# CANtoCAN.net
KiCad netlist of a schematic drawn in Altium Designer
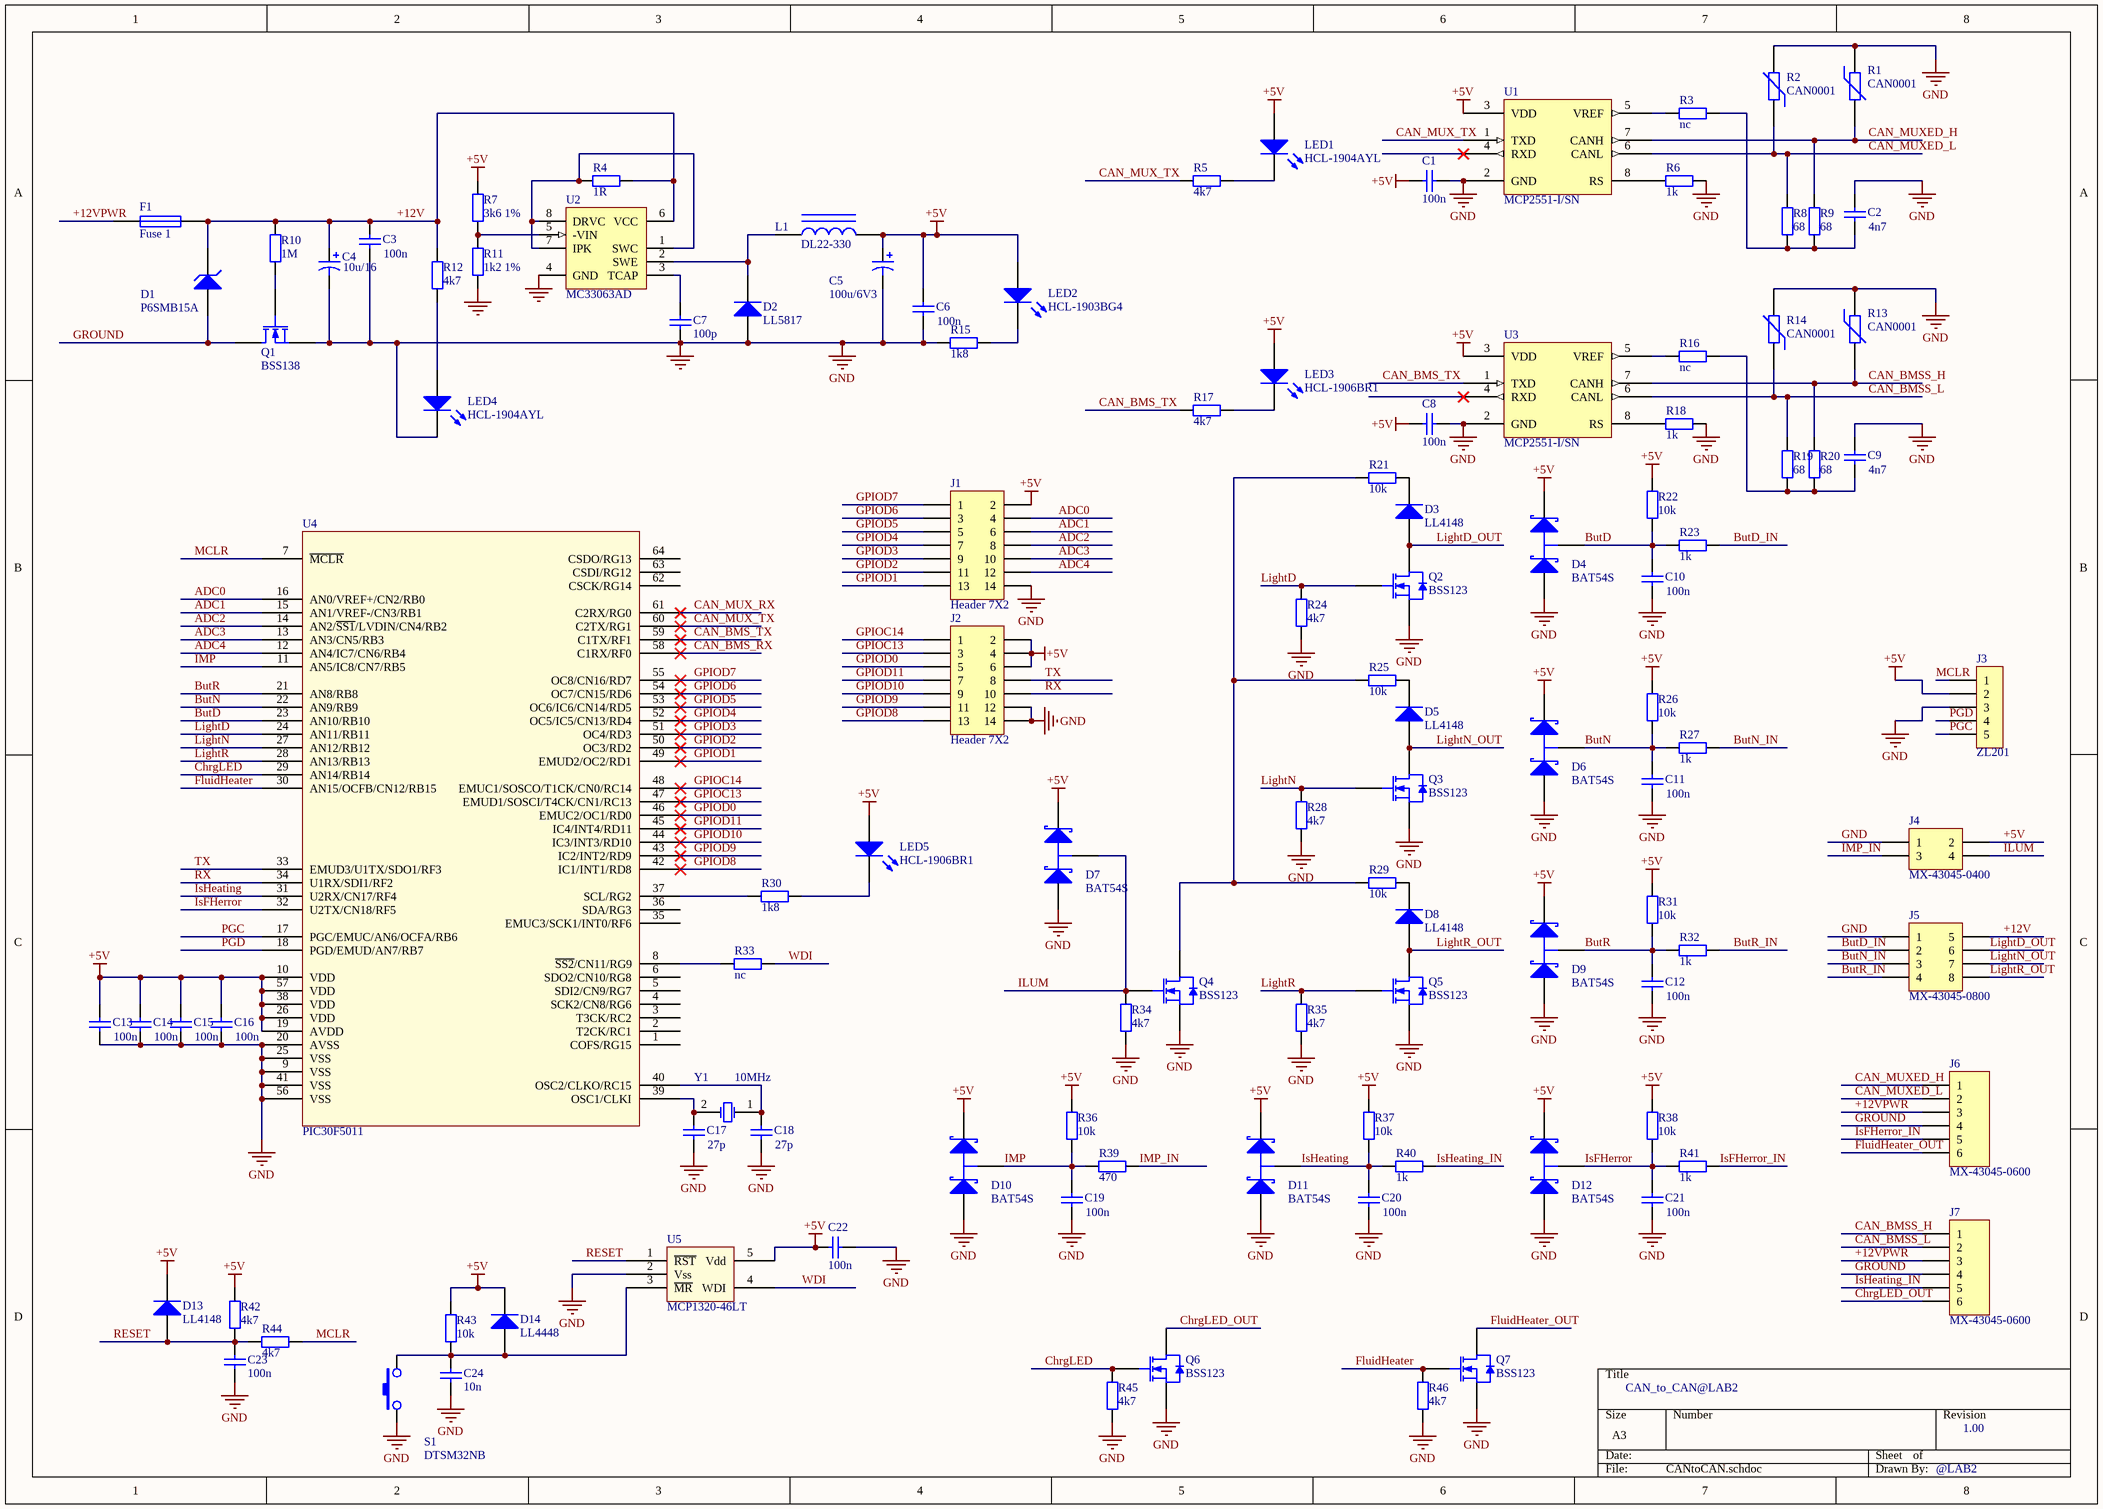
[diagram p0: CANtoCAN.schdoc]

(export (version "E")
  (design (tool "Eeschema 10.0.6"))
  (components
    (comp (ref "C1")
      (value "100n")
      (footprint "0603")
      (description "Capacitor")
      (libsource (lib "Miscellaneous Devices") (part "Cap"))
    )
    (comp (ref "C2")
      (value "4n7")
      (footprint "0603")
      (description "Capacitor")
      (libsource (lib "Miscellaneous Devices") (part "Cap"))
    )
    (comp (ref "C3")
      (value "100n")
      (footprint "0402-A")
      (description "Capacitor")
      (libsource (lib "Miscellaneous Devices") (part "Cap"))
    )
    (comp (ref "C4")
      (value "10u/16")
      (footprint "0402-A")
      (description "Polarized Capacitor (Radial)")
      (libsource (lib "Miscellaneous Devices") (part "Cap Pol1"))
    )
    (comp (ref "C5")
      (value "100u/6V3")
      (footprint "0402-A")
      (description "Polarized Capacitor (Radial)")
      (libsource (lib "Miscellaneous Devices") (part "Cap Pol1"))
    )
    (comp (ref "C6")
      (value "100n")
      (footprint "0603")
      (description "Capacitor")
      (libsource (lib "Miscellaneous Devices") (part "Cap"))
    )
    (comp (ref "C7")
      (value "100p")
      (footprint "0603")
      (description "Capacitor")
      (libsource (lib "Miscellaneous Devices") (part "Cap"))
    )
    (comp (ref "C8")
      (value "100n")
      (footprint "0603")
      (description "Capacitor")
      (libsource (lib "Miscellaneous Devices") (part "Cap"))
    )
    (comp (ref "C9")
      (value "4n7")
      (footprint "0603")
      (description "Capacitor")
      (libsource (lib "Miscellaneous Devices") (part "Cap"))
    )
    (comp (ref "C10")
      (value "100n")
      (footprint "0603")
      (description "Capacitor")
      (libsource (lib "Miscellaneous Devices") (part "Cap"))
    )
    (comp (ref "C11")
      (value "100n")
      (footprint "0603")
      (description "Capacitor")
      (libsource (lib "Miscellaneous Devices") (part "Cap"))
    )
    (comp (ref "C12")
      (value "100n")
      (footprint "0603")
      (description "Capacitor")
      (libsource (lib "Miscellaneous Devices") (part "Cap"))
    )
    (comp (ref "C13")
      (value "100n")
      (footprint "0603")
      (description "Capacitor")
      (libsource (lib "Miscellaneous Devices") (part "Cap"))
    )
    (comp (ref "C14")
      (value "100n")
      (footprint "0603")
      (description "Capacitor")
      (libsource (lib "Miscellaneous Devices") (part "Cap"))
    )
    (comp (ref "C15")
      (value "100n")
      (footprint "0603")
      (description "Capacitor")
      (libsource (lib "Miscellaneous Devices") (part "Cap"))
    )
    (comp (ref "C16")
      (value "100n")
      (footprint "0603")
      (description "Capacitor")
      (libsource (lib "Miscellaneous Devices") (part "Cap"))
    )
    (comp (ref "C17")
      (value "27p")
      (footprint "0603")
      (description "Capacitor")
      (libsource (lib "Miscellaneous Devices") (part "Cap"))
    )
    (comp (ref "C18")
      (value "27p")
      (footprint "0603")
      (description "Capacitor")
      (libsource (lib "Miscellaneous Devices") (part "Cap"))
    )
    (comp (ref "C19")
      (value "100n")
      (footprint "0603")
      (description "Capacitor")
      (libsource (lib "Miscellaneous Devices") (part "Cap"))
    )
    (comp (ref "C20")
      (value "100n")
      (footprint "0603")
      (description "Capacitor")
      (libsource (lib "Miscellaneous Devices") (part "Cap"))
    )
    (comp (ref "C21")
      (value "100n")
      (footprint "0603")
      (description "Capacitor")
      (libsource (lib "Miscellaneous Devices") (part "Cap"))
    )
    (comp (ref "C22")
      (value "100n")
      (footprint "0603")
      (description "Capacitor")
      (libsource (lib "Miscellaneous Devices") (part "Cap"))
    )
    (comp (ref "C23")
      (value "100n")
      (footprint "0603")
      (description "Capacitor")
      (libsource (lib "Miscellaneous Devices") (part "Cap"))
    )
    (comp (ref "C24")
      (value "10n")
      (footprint "0603")
      (description "Capacitor")
      (libsource (lib "Miscellaneous Devices") (part "Cap"))
    )
    (comp (ref "D1")
      (value "P6SMB15A")
      (footprint "6-0805_M")
      (description "Zener Diode")
      (libsource (lib "Miscellaneous Devices") (part "D Zener"))
    )
    (comp (ref "D2")
      (value "LL5817")
      (footprint "6-0805_M")
      (description "High Conductance Fast Diode")
      (libsource (lib "FSC Discrete Diode") (part "1N4148"))
    )
    (comp (ref "D3")
      (value "LL4148")
      (footprint "6-0805_N")
      (description "High Conductance Fast Diode")
      (libsource (lib "FSC Discrete Diode") (part "1N4148"))
    )
    (comp (ref "D4")
      (value "BAT54S")
      (footprint "SOT23_M")
      (description "Schottky Barrier Double Diode")
      (libsource (lib "Philips Discrete Diode - Schottky") (part "BAT54S"))
    )
    (comp (ref "D5")
      (value "LL4148")
      (footprint "3.2X1.6X1.1")
      (description "High Conductance Fast Diode")
      (libsource (lib "FSC Discrete Diode") (part "1N4148"))
    )
    (comp (ref "D6")
      (value "BAT54S")
      (footprint "SOT-23B_M")
      (description "Schottky Barrier Double Diode")
      (libsource (lib "Philips Discrete Diode - Schottky") (part "BAT54S"))
    )
    (comp (ref "D7")
      (value "BAT54S")
      (footprint "SOT23_N")
      (description "Schottky Barrier Double Diode")
      (libsource (lib "Philips Discrete Diode - Schottky") (part "BAT54S"))
    )
    (comp (ref "D8")
      (value "LL4148")
      (footprint "3.2X1.6X1.1")
      (description "High Conductance Fast Diode")
      (libsource (lib "FSC Discrete Diode") (part "1N4148"))
    )
    (comp (ref "D9")
      (value "BAT54S")
      (footprint "SOT23_M")
      (description "Schottky Barrier Double Diode")
      (libsource (lib "Philips Discrete Diode - Schottky") (part "BAT54S"))
    )
    (comp (ref "D10")
      (value "BAT54S")
      (footprint "SOT23_M")
      (description "Schottky Barrier Double Diode")
      (libsource (lib "Philips Discrete Diode - Schottky") (part "BAT54S"))
    )
    (comp (ref "D11")
      (value "BAT54S")
      (footprint "SOT23_M")
      (description "Schottky Barrier Double Diode")
      (libsource (lib "Philips Discrete Diode - Schottky") (part "BAT54S"))
    )
    (comp (ref "D12")
      (value "BAT54S")
      (footprint "SOT23_N")
      (description "Schottky Barrier Double Diode")
      (libsource (lib "Philips Discrete Diode - Schottky") (part "BAT54S"))
    )
    (comp (ref "D13")
      (value "LL4148")
      (footprint "6-0805_M")
      (description "High Conductance Fast Diode")
      (libsource (lib "FSC Discrete Diode") (part "1N4148"))
    )
    (comp (ref "D14")
      (value "LL4448")
      (footprint "3.2X1.6X1.1")
      (description "Default Diode")
      (libsource (lib "Miscellaneous Devices") (part "Diode"))
    )
    (comp (ref "F1")
      (value "Fuse 1")
      (footprint "6-0805_N")
      (description "Fuse")
      (libsource (lib "Miscellaneous Devices") (part "Fuse 1"))
    )
    (comp (ref "J1")
      (value "Header 7X2")
      (footprint "HDR2X7")
      (description "Header, 7-Pin, Dual row")
      (libsource (lib "Miscellaneous Connectors") (part "Header 7X2"))
    )
    (comp (ref "J2")
      (value "Header 7X2")
      (footprint "HDR2X7")
      (description "Header, 7-Pin, Dual row")
      (libsource (lib "Miscellaneous Connectors") (part "Header 7X2"))
    )
    (comp (ref "J3")
      (value "ZL201")
      (footprint "HDR1X5")
      (description "Connector")
      (libsource (lib "*") (part "CON5"))
    )
    (comp (ref "J4")
      (value "MX-43045-0400")
      (footprint "MHDR2X2")
      (description "Header, 2-Pin, Dual row")
      (libsource (lib "Miscellaneous Connectors") (part "Header 2X2"))
    )
    (comp (ref "J5")
      (value "MX-43045-0800")
      (footprint "HDR2X4")
      (description "Header, 4-Pin, Dual row")
      (libsource (lib "Miscellaneous Connectors") (part "Header 4X2A"))
    )
    (comp (ref "J6")
      (value "MX-43045-0600")
      (footprint "HDR1X8")
      (description "Header, 6-Pin")
      (libsource (lib "Miscellaneous Connectors") (part "Header 6"))
    )
    (comp (ref "J7")
      (value "MX-43045-0600")
      (footprint "MHDR1X6")
      (description "Header, 6-Pin")
      (libsource (lib "Miscellaneous Connectors") (part "Header 6"))
    )
    (comp (ref "L1")
      (value "DL22-330")
      (footprint "0402-A")
      (description "Magnetic-Core Inductor")
      (libsource (lib "Miscellaneous Devices") (part "Inductor Iron"))
    )
    (comp (ref "LED1")
      (value "HCL-1904AYL")
      (footprint "0603")
      (description "Typical BLUE SiC LED")
      (libsource (lib "Miscellaneous Devices") (part "LED3"))
    )
    (comp (ref "LED2")
      (value "HCL-1903BG4")
      (footprint "0603")
      (description "Typical BLUE SiC LED")
      (libsource (lib "Miscellaneous Devices") (part "LED3"))
    )
    (comp (ref "LED3")
      (value "HCL-1906BR1")
      (footprint "0603")
      (description "Typical BLUE SiC LED")
      (libsource (lib "Miscellaneous Devices") (part "LED3"))
    )
    (comp (ref "LED4")
      (value "HCL-1904AYL")
      (footprint "6-0805_M")
      (description "Typical BLUE SiC LED")
      (libsource (lib "Miscellaneous Devices") (part "LED3"))
    )
    (comp (ref "LED5")
      (value "HCL-1906BR1")
      (footprint "0603")
      (description "Typical BLUE SiC LED")
      (libsource (lib "Miscellaneous Devices") (part "LED3"))
    )
    (comp (ref "Q1")
      (value "BSS138")
      (footprint "SOT23_N")
      (description "N-Channel Enhancement Mode Vertical DMOS FET")
      (libsource (lib "Zetex Discrete MOSFET") (part "BSS138"))
    )
    (comp (ref "Q2")
      (value "BSS123")
      (footprint "SOT23_N")
      (description "N-channel Enhancement Mode Vertical D-MOSFET")
      (libsource (lib "Philips Discrete MOSFET - Low Power") (part "BSS123"))
    )
    (comp (ref "Q3")
      (value "BSS123")
      (footprint "SOT23_M")
      (description "N-channel Enhancement Mode Vertical D-MOSFET")
      (libsource (lib "Philips Discrete MOSFET - Low Power") (part "BSS123"))
    )
    (comp (ref "Q4")
      (value "BSS123")
      (footprint "SOT23_N")
      (description "N-channel Enhancement Mode Vertical D-MOSFET")
      (libsource (lib "Philips Discrete MOSFET - Low Power") (part "BSS123"))
    )
    (comp (ref "Q5")
      (value "BSS123")
      (footprint "SOT23_L")
      (description "N-channel Enhancement Mode Vertical D-MOSFET")
      (libsource (lib "Philips Discrete MOSFET - Low Power") (part "BSS123"))
    )
    (comp (ref "Q6")
      (value "BSS123")
      (footprint "SOT23_N")
      (description "N-channel Enhancement Mode Vertical D-MOSFET")
      (libsource (lib "Philips Discrete MOSFET - Low Power") (part "BSS123"))
    )
    (comp (ref "Q7")
      (value "BSS123")
      (footprint "SOT23_N")
      (description "N-channel Enhancement Mode Vertical D-MOSFET")
      (libsource (lib "Philips Discrete MOSFET - Low Power") (part "BSS123"))
    )
    (comp (ref "R1")
      (value "CAN0001")
      (footprint "0603")
      (description "Varistor (Voltage-Sensitive Resistor)")
      (libsource (lib "Miscellaneous Devices") (part "Res Varistor"))
    )
    (comp (ref "R2")
      (value "CAN0001")
      (footprint "0603")
      (description "Varistor (Voltage-Sensitive Resistor)")
      (libsource (lib "Miscellaneous Devices") (part "Res Varistor"))
    )
    (comp (ref "R3")
      (value "nc")
      (footprint "0603")
      (description "Resistor")
      (libsource (lib "") (part "Res2_1"))
    )
    (comp (ref "R4")
      (value "1R")
      (footprint "0603")
      (description "Resistor")
      (libsource (lib "") (part "Res2_1"))
    )
    (comp (ref "R5")
      (value "4k7")
      (footprint "0603")
      (description "Resistor")
      (libsource (lib "Miscellaneous Devices") (part "Res2"))
    )
    (comp (ref "R6")
      (value "1k")
      (footprint "0603")
      (description "Resistor")
      (libsource (lib "") (part "Res2_1"))
    )
    (comp (ref "R7")
      (value "3k6 1%")
      (footprint "0603")
      (description "Resistor")
      (libsource (lib "") (part "Res2_2"))
    )
    (comp (ref "R8")
      (value "68")
      (footprint "0603")
      (description "Resistor")
      (libsource (lib "") (part "Res2_2"))
    )
    (comp (ref "R9")
      (value "68")
      (footprint "0603")
      (description "Resistor")
      (libsource (lib "") (part "Res2_2"))
    )
    (comp (ref "R10")
      (value "1M")
      (footprint "0603")
      (description "Resistor")
      (libsource (lib "") (part "Res2_2"))
    )
    (comp (ref "R11")
      (value "1k2 1%")
      (footprint "0603")
      (description "Resistor")
      (libsource (lib "") (part "Res2_3"))
    )
    (comp (ref "R12")
      (value "4k7")
      (footprint "0603")
      (description "Resistor")
      (libsource (lib "") (part "Res2_2"))
    )
    (comp (ref "R13")
      (value "CAN0001")
      (footprint "0603")
      (description "Varistor (Voltage-Sensitive Resistor)")
      (libsource (lib "Miscellaneous Devices") (part "Res Varistor"))
    )
    (comp (ref "R14")
      (value "CAN0001")
      (footprint "0603")
      (description "Varistor (Voltage-Sensitive Resistor)")
      (libsource (lib "Miscellaneous Devices") (part "Res Varistor"))
    )
    (comp (ref "R15")
      (value "1k8")
      (footprint "0603")
      (description "Resistor")
      (libsource (lib "Miscellaneous Devices") (part "Res2"))
    )
    (comp (ref "R16")
      (value "nc")
      (footprint "0603")
      (description "Resistor")
      (libsource (lib "") (part "Res2_1"))
    )
    (comp (ref "R17")
      (value "4k7")
      (footprint "0603")
      (description "Resistor")
      (libsource (lib "Miscellaneous Devices") (part "Res2"))
    )
    (comp (ref "R18")
      (value "1k")
      (footprint "0603")
      (description "Resistor")
      (libsource (lib "") (part "Res2_1"))
    )
    (comp (ref "R19")
      (value "68")
      (footprint "0603")
      (description "Resistor")
      (libsource (lib "") (part "Res2_2"))
    )
    (comp (ref "R20")
      (value "68")
      (footprint "0603")
      (description "Resistor")
      (libsource (lib "") (part "Res2_2"))
    )
    (comp (ref "R21")
      (value "10k")
      (footprint "0603")
      (description "Resistor")
      (libsource (lib "") (part "Res2_1"))
    )
    (comp (ref "R22")
      (value "10k")
      (footprint "0603")
      (description "Resistor")
      (libsource (lib "") (part "Res2_2"))
    )
    (comp (ref "R23")
      (value "1k")
      (footprint "0603")
      (description "Resistor")
      (libsource (lib "Miscellaneous Devices") (part "Res2"))
    )
    (comp (ref "R24")
      (value "4k7")
      (footprint "0603")
      (description "Resistor")
      (libsource (lib "") (part "Res2_2"))
    )
    (comp (ref "R25")
      (value "10k")
      (footprint "0603")
      (description "Resistor")
      (libsource (lib "") (part "Res2_1"))
    )
    (comp (ref "R26")
      (value "10k")
      (footprint "0603")
      (description "Resistor")
      (libsource (lib "") (part "Res2_2"))
    )
    (comp (ref "R27")
      (value "1k")
      (footprint "0603")
      (description "Resistor")
      (libsource (lib "Miscellaneous Devices") (part "Res2"))
    )
    (comp (ref "R28")
      (value "4k7")
      (footprint "0603")
      (description "Resistor")
      (libsource (lib "") (part "Res2_2"))
    )
    (comp (ref "R29")
      (value "10k")
      (footprint "0603")
      (description "Resistor")
      (libsource (lib "") (part "Res2_1"))
    )
    (comp (ref "R30")
      (value "1k8")
      (footprint "0603")
      (description "Resistor")
      (libsource (lib "Miscellaneous Devices") (part "Res2"))
    )
    (comp (ref "R31")
      (value "10k")
      (footprint "0603")
      (description "Resistor")
      (libsource (lib "") (part "Res2_2"))
    )
    (comp (ref "R32")
      (value "1k")
      (footprint "0603")
      (description "Resistor")
      (libsource (lib "Miscellaneous Devices") (part "Res2"))
    )
    (comp (ref "R33")
      (value "nc")
      (footprint "0603")
      (description "Resistor")
      (libsource (lib "Miscellaneous Devices") (part "Res2"))
    )
    (comp (ref "R34")
      (value "4k7")
      (footprint "0603")
      (description "Resistor")
      (libsource (lib "") (part "Res2_2"))
    )
    (comp (ref "R35")
      (value "4k7")
      (footprint "0603")
      (description "Resistor")
      (libsource (lib "") (part "Res2_2"))
    )
    (comp (ref "R36")
      (value "10k")
      (footprint "0603")
      (description "Resistor")
      (libsource (lib "") (part "Res2_2"))
    )
    (comp (ref "R37")
      (value "10k")
      (footprint "0603")
      (description "Resistor")
      (libsource (lib "") (part "Res2_2"))
    )
    (comp (ref "R38")
      (value "10k")
      (footprint "0603")
      (description "Resistor")
      (libsource (lib "") (part "Res2_2"))
    )
    (comp (ref "R39")
      (value "470")
      (footprint "0603")
      (description "Resistor")
      (libsource (lib "Miscellaneous Devices") (part "Res2"))
    )
    (comp (ref "R40")
      (value "1k")
      (footprint "0603")
      (description "Resistor")
      (libsource (lib "Miscellaneous Devices") (part "Res2"))
    )
    (comp (ref "R41")
      (value "1k")
      (footprint "0603")
      (description "Resistor")
      (libsource (lib "Miscellaneous Devices") (part "Res2"))
    )
    (comp (ref "R42")
      (value "4k7")
      (footprint "0603")
      (description "Resistor")
      (libsource (lib "") (part "Res2_2"))
    )
    (comp (ref "R43")
      (value "10k")
      (footprint "0603")
      (description "Resistor")
      (libsource (lib "") (part "Res2_3"))
    )
    (comp (ref "R44")
      (value "4k7")
      (footprint "0603")
      (description "Resistor")
      (libsource (lib "Miscellaneous Devices") (part "Res2"))
    )
    (comp (ref "R45")
      (value "4k7")
      (footprint "0603")
      (description "Resistor")
      (libsource (lib "") (part "Res2_2"))
    )
    (comp (ref "R46")
      (value "4k7")
      (footprint "0603")
      (description "Resistor")
      (libsource (lib "") (part "Res2_2"))
    )
    (comp (ref "S1")
      (value "DTSM32NB")
      (footprint "0402")
      (description "Switch PushButton")
      (libsource (lib "*") (part "PUSHB"))
    )
    (comp (ref "U1")
      (value "MCP2551-I/SN")
      (footprint "SO8_L")
      (description "High Speed CAN Transceiver, 8-Pin Plastic SOIC, Industrial Grade")
      (libsource (lib "Microchip Interface Line Transceiver") (part "MCP2551-I/SN"))
    )
    (comp (ref "U2")
      (value "MC33063AD")
      (footprint "SO8_N")
      (description "DC-to-DC Converter Control Circuit")
      (libsource (lib "Motorola Power Mgt DC-DC Converter") (part "MC33063AD"))
    )
    (comp (ref "U3")
      (value "MCP2551-I/SN")
      (footprint "SO8_L")
      (description "High Speed CAN Transceiver, 8-Pin Plastic SOIC, Industrial Grade")
      (libsource (lib "Microchip Interface Line Transceiver") (part "MCP2551-I/SN"))
    )
    (comp (ref "U4")
      (value "PIC30F5011")
      (footprint "QFP80P1600X1600X120-64N")
      (description "PIC30F5011 - Up")
      (libsource (lib "X-Tro's Misc") (part "PIC30F5011"))
    )
    (comp (ref "U5")
      (value "MCP1320-46LT")
      (footprint "SOP5(6)")
      (libsource (lib "X-Tro's Misc") (part "MCP1320"))
    )
    (comp (ref "Y1")
      (value "10MHz")
      (footprint "AXIAL-0.3")
      (description "Crystal Oscillator")
      (libsource (lib "Miscellaneous Devices") (part "XTAL"))
    )
  )
  (nets
    (net (code "1") (name "+5V") (class "Default")
      (node (ref "C1") (pin "1") (pinfunction "1_1") (pintype "passive"))
      (node (ref "C13") (pin "1") (pinfunction "1_1") (pintype "passive"))
      (node (ref "C14") (pin "1") (pinfunction "1_1") (pintype "passive"))
      (node (ref "C15") (pin "1") (pinfunction "1_1") (pintype "passive"))
      (node (ref "C16") (pin "1") (pinfunction "1_1") (pintype "passive"))
      (node (ref "C22") (pin "1") (pinfunction "1_1") (pintype "passive"))
      (node (ref "C5") (pin "1") (pinfunction "1_1") (pintype "passive"))
      (node (ref "C6") (pin "1") (pinfunction "1_1") (pintype "passive"))
      (node (ref "C8") (pin "1") (pinfunction "1_1") (pintype "passive"))
      (node (ref "D10") (pin "2") (pinfunction "K_2") (pintype "passive"))
      (node (ref "D11") (pin "2") (pinfunction "K_2") (pintype "passive"))
      (node (ref "D12") (pin "2") (pinfunction "K_2") (pintype "passive"))
      (node (ref "D13") (pin "2") (pinfunction "K_2") (pintype "passive"))
      (node (ref "D14") (pin "2") (pinfunction "K_2") (pintype "passive"))
      (node (ref "D4") (pin "2") (pinfunction "K_2") (pintype "passive"))
      (node (ref "D6") (pin "2") (pinfunction "K_2") (pintype "passive"))
      (node (ref "D7") (pin "2") (pinfunction "K_2") (pintype "passive"))
      (node (ref "D9") (pin "2") (pinfunction "K_2") (pintype "passive"))
      (node (ref "J1") (pin "2") (pinfunction "2_2") (pintype "passive"))
      (node (ref "J2") (pin "2") (pinfunction "2_2") (pintype "passive"))
      (node (ref "J2") (pin "4") (pinfunction "4_4") (pintype "passive"))
      (node (ref "J2") (pin "6") (pinfunction "6_6") (pintype "passive"))
      (node (ref "J3") (pin "2") (pinfunction "2_2") (pintype "passive"))
      (node (ref "J4") (pin "2") (pinfunction "2_2") (pintype "passive"))
      (node (ref "L1") (pin "2") (pinfunction "2_2") (pintype "passive"))
      (node (ref "LED1") (pin "1") (pinfunction "A_1") (pintype "passive"))
      (node (ref "LED2") (pin "1") (pinfunction "A_1") (pintype "passive"))
      (node (ref "LED3") (pin "1") (pinfunction "A_1") (pintype "passive"))
      (node (ref "LED5") (pin "1") (pinfunction "A_1") (pintype "passive"))
      (node (ref "R22") (pin "1") (pinfunction "1_1") (pintype "passive"))
      (node (ref "R26") (pin "1") (pinfunction "1_1") (pintype "passive"))
      (node (ref "R31") (pin "1") (pinfunction "1_1") (pintype "passive"))
      (node (ref "R36") (pin "1") (pinfunction "1_1") (pintype "passive"))
      (node (ref "R37") (pin "1") (pinfunction "1_1") (pintype "passive"))
      (node (ref "R38") (pin "1") (pinfunction "1_1") (pintype "passive"))
      (node (ref "R42") (pin "1") (pinfunction "1_1") (pintype "passive"))
      (node (ref "R43") (pin "2") (pinfunction "2_2") (pintype "passive"))
      (node (ref "R7") (pin "1") (pinfunction "1_1") (pintype "passive"))
      (node (ref "U1") (pin "3") (pinfunction "VDD_3") (pintype "power_in"))
      (node (ref "U3") (pin "3") (pinfunction "VDD_3") (pintype "power_in"))
      (node (ref "U4") (pin "10") (pinfunction "VDD_10") (pintype "passive"))
      (node (ref "U4") (pin "19") (pinfunction "AVDD_19") (pintype "passive"))
      (node (ref "U4") (pin "26") (pinfunction "VDD_26") (pintype "passive"))
      (node (ref "U4") (pin "38") (pinfunction "VDD_38") (pintype "passive"))
      (node (ref "U4") (pin "57") (pinfunction "VDD_57") (pintype "passive"))
      (node (ref "U5") (pin "5") (pinfunction "Vdd_5") (pintype "passive"))
    )
    (net (code "2") (name "/+12V") (class "Default")
      (node (ref "C3") (pin "1") (pinfunction "1_1") (pintype "passive"))
      (node (ref "C4") (pin "1") (pinfunction "1_1") (pintype "passive"))
      (node (ref "D1") (pin "2") (pinfunction "K_2") (pintype "passive"))
      (node (ref "F1") (pin "2") (pinfunction "2_2") (pintype "passive"))
      (node (ref "J5") (pin "5") (pinfunction "5_5") (pintype "passive"))
      (node (ref "R10") (pin "1") (pinfunction "1_1") (pintype "passive"))
      (node (ref "R12") (pin "1") (pinfunction "1_1") (pintype "passive"))
      (node (ref "R4") (pin "2") (pinfunction "2_2") (pintype "passive"))
      (node (ref "U2") (pin "6") (pinfunction "VCC_6") (pintype "power_in"))
    )
    (net (code "3") (name "/+12VPWR") (class "Default")
      (node (ref "F1") (pin "1") (pinfunction "1_1") (pintype "passive"))
      (node (ref "J6") (pin "3") (pinfunction "3_3") (pintype "passive"))
      (node (ref "J7") (pin "3") (pinfunction "3_3") (pintype "passive"))
    )
    (net (code "4") (name "/ADC0") (class "Default")
      (node (ref "J1") (pin "4") (pinfunction "4_4") (pintype "passive"))
      (node (ref "U4") (pin "16") (pinfunction "AN0/VREF+/CN2/RB0_16") (pintype "passive"))
    )
    (net (code "5") (name "/ADC1") (class "Default")
      (node (ref "J1") (pin "6") (pinfunction "6_6") (pintype "passive"))
      (node (ref "U4") (pin "15") (pinfunction "AN1/VREF-/CN3/RB1_15") (pintype "passive"))
    )
    (net (code "6") (name "/ADC2") (class "Default")
      (node (ref "J1") (pin "8") (pinfunction "8_8") (pintype "passive"))
      (node (ref "U4") (pin "14") (pinfunction "AN2/~{SS1}/LVDIN/CN4/RB2_14") (pintype "passive"))
    )
    (net (code "7") (name "/ADC3") (class "Default")
      (node (ref "J1") (pin "10") (pinfunction "10_10") (pintype "passive"))
      (node (ref "U4") (pin "13") (pinfunction "AN3/CN5/RB3_13") (pintype "passive"))
    )
    (net (code "8") (name "/ADC4") (class "Default")
      (node (ref "J1") (pin "12") (pinfunction "12_12") (pintype "passive"))
      (node (ref "U4") (pin "12") (pinfunction "AN4/IC7/CN6/RB4_12") (pintype "passive"))
    )
    (net (code "9") (name "/ButD") (class "Default")
      (node (ref "C10") (pin "1") (pinfunction "1_1") (pintype "passive"))
      (node (ref "D4") (pin "3") (pinfunction "C_3") (pintype "passive"))
      (node (ref "R22") (pin "2") (pinfunction "2_2") (pintype "passive"))
      (node (ref "R23") (pin "2") (pinfunction "2_2") (pintype "passive"))
      (node (ref "U4") (pin "23") (pinfunction "AN10/RB10_23") (pintype "passive"))
    )
    (net (code "10") (name "/ButD_IN") (class "Default")
      (node (ref "J5") (pin "2") (pinfunction "2_2") (pintype "passive"))
      (node (ref "R23") (pin "1") (pinfunction "1_1") (pintype "passive"))
    )
    (net (code "11") (name "/ButN") (class "Default")
      (node (ref "C11") (pin "1") (pinfunction "1_1") (pintype "passive"))
      (node (ref "D6") (pin "3") (pinfunction "C_3") (pintype "passive"))
      (node (ref "R26") (pin "2") (pinfunction "2_2") (pintype "passive"))
      (node (ref "R27") (pin "2") (pinfunction "2_2") (pintype "passive"))
      (node (ref "U4") (pin "22") (pinfunction "AN9/RB9_22") (pintype "passive"))
    )
    (net (code "12") (name "/ButN_IN") (class "Default")
      (node (ref "J5") (pin "3") (pinfunction "3_3") (pintype "passive"))
      (node (ref "R27") (pin "1") (pinfunction "1_1") (pintype "passive"))
    )
    (net (code "13") (name "/ButR") (class "Default")
      (node (ref "C12") (pin "1") (pinfunction "1_1") (pintype "passive"))
      (node (ref "D9") (pin "3") (pinfunction "C_3") (pintype "passive"))
      (node (ref "R31") (pin "2") (pinfunction "2_2") (pintype "passive"))
      (node (ref "R32") (pin "2") (pinfunction "2_2") (pintype "passive"))
      (node (ref "U4") (pin "21") (pinfunction "AN8/RB8_21") (pintype "passive"))
    )
    (net (code "14") (name "/ButR_IN") (class "Default")
      (node (ref "J5") (pin "4") (pinfunction "4_4") (pintype "passive"))
      (node (ref "R32") (pin "1") (pinfunction "1_1") (pintype "passive"))
    )
    (net (code "15") (name "/CAN_BMSS_H") (class "Default")
      (node (ref "J7") (pin "1") (pinfunction "1_1") (pintype "passive"))
      (node (ref "R13") (pin "2") (pinfunction "2_2") (pintype "passive"))
      (node (ref "R20") (pin "1") (pinfunction "1_1") (pintype "passive"))
      (node (ref "U3") (pin "7") (pinfunction "CANH_7") (pintype "output"))
    )
    (net (code "16") (name "/CAN_BMSS_L") (class "Default")
      (node (ref "J7") (pin "2") (pinfunction "2_2") (pintype "passive"))
      (node (ref "R14") (pin "1") (pinfunction "1_1") (pintype "passive"))
      (node (ref "R19") (pin "1") (pinfunction "1_1") (pintype "passive"))
      (node (ref "U3") (pin "6") (pinfunction "CANL_6") (pintype "output"))
    )
    (net (code "17") (name "/CAN_BMS_RX") (class "Default")
      (node (ref "U4") (pin "58") (pinfunction "C1RX/RF0_58") (pintype "passive+no_connect"))
    )
    (net (code "18") (name "/CAN_BMS_TX") (class "Default")
      (node (ref "R17") (pin "2") (pinfunction "2_2") (pintype "passive"))
      (node (ref "U3") (pin "1") (pinfunction "TXD_1") (pintype "input"))
      (node (ref "U4") (pin "59") (pinfunction "C1TX/RF1_59") (pintype "passive"))
    )
    (net (code "19") (name "/CAN_MUXED_H") (class "Default")
      (node (ref "J6") (pin "1") (pinfunction "1_1") (pintype "passive"))
      (node (ref "R1") (pin "2") (pinfunction "2_2") (pintype "passive"))
      (node (ref "R9") (pin "1") (pinfunction "1_1") (pintype "passive"))
      (node (ref "U1") (pin "7") (pinfunction "CANH_7") (pintype "output"))
    )
    (net (code "20") (name "/CAN_MUXED_L") (class "Default")
      (node (ref "J6") (pin "2") (pinfunction "2_2") (pintype "passive"))
      (node (ref "R2") (pin "1") (pinfunction "1_1") (pintype "passive"))
      (node (ref "R8") (pin "1") (pinfunction "1_1") (pintype "passive"))
      (node (ref "U1") (pin "6") (pinfunction "CANL_6") (pintype "output"))
    )
    (net (code "21") (name "/CAN_MUX_RX") (class "Default")
      (node (ref "U4") (pin "61") (pinfunction "C2RX/RG0_61") (pintype "passive+no_connect"))
    )
    (net (code "22") (name "/CAN_MUX_TX") (class "Default")
      (node (ref "R5") (pin "2") (pinfunction "2_2") (pintype "passive"))
      (node (ref "U1") (pin "1") (pinfunction "TXD_1") (pintype "input"))
      (node (ref "U4") (pin "60") (pinfunction "C2TX/RG1_60") (pintype "passive"))
    )
    (net (code "23") (name "/ChrgLED") (class "Default")
      (node (ref "Q6") (pin "3") (pinfunction "G_3") (pintype "passive"))
      (node (ref "R45") (pin "1") (pinfunction "1_1") (pintype "passive"))
      (node (ref "U4") (pin "29") (pinfunction "AN14/RB14_29") (pintype "passive"))
    )
    (net (code "24") (name "/ChrgLED_OUT") (class "Default")
      (node (ref "J7") (pin "6") (pinfunction "6_6") (pintype "passive"))
      (node (ref "Q6") (pin "1") (pinfunction "D_1") (pintype "passive"))
    )
    (net (code "25") (name "/FluidHeater") (class "Default")
      (node (ref "Q7") (pin "3") (pinfunction "G_3") (pintype "passive"))
      (node (ref "R46") (pin "1") (pinfunction "1_1") (pintype "passive"))
      (node (ref "U4") (pin "30") (pinfunction "AN15/OCFB/CN12/RB15_30") (pintype "passive"))
    )
    (net (code "26") (name "/FluidHeater_OUT") (class "Default")
      (node (ref "J6") (pin "6") (pinfunction "6_6") (pintype "passive"))
      (node (ref "Q7") (pin "1") (pinfunction "D_1") (pintype "passive"))
    )
    (net (code "27") (name "/GPIOC13") (class "Default")
      (node (ref "J2") (pin "3") (pinfunction "3_3") (pintype "passive"))
      (node (ref "U4") (pin "47") (pinfunction "EMUD1/SOSCI/T4CK/CN1/RC13_47") (pintype "passive"))
    )
    (net (code "28") (name "/GPIOC14") (class "Default")
      (node (ref "J2") (pin "1") (pinfunction "1_1") (pintype "passive"))
      (node (ref "U4") (pin "48") (pinfunction "EMUC1/SOSCO/T1CK/CN0/RC14_48") (pintype "passive"))
    )
    (net (code "29") (name "/GPIOD0") (class "Default")
      (node (ref "J2") (pin "5") (pinfunction "5_5") (pintype "passive"))
      (node (ref "U4") (pin "46") (pinfunction "EMUC2/OC1/RD0_46") (pintype "passive"))
    )
    (net (code "30") (name "/GPIOD1") (class "Default")
      (node (ref "J1") (pin "13") (pinfunction "13_13") (pintype "passive"))
      (node (ref "U4") (pin "49") (pinfunction "EMUD2/OC2/RD1_49") (pintype "passive"))
    )
    (net (code "31") (name "/GPIOD2") (class "Default")
      (node (ref "J1") (pin "11") (pinfunction "11_11") (pintype "passive"))
      (node (ref "U4") (pin "50") (pinfunction "OC3/RD2_50") (pintype "passive"))
    )
    (net (code "32") (name "/GPIOD3") (class "Default")
      (node (ref "J1") (pin "9") (pinfunction "9_9") (pintype "passive"))
      (node (ref "U4") (pin "51") (pinfunction "OC4/RD3_51") (pintype "passive"))
    )
    (net (code "33") (name "/GPIOD4") (class "Default")
      (node (ref "J1") (pin "7") (pinfunction "7_7") (pintype "passive"))
      (node (ref "U4") (pin "52") (pinfunction "OC5/IC5/CN13/RD4_52") (pintype "passive"))
    )
    (net (code "34") (name "/GPIOD5") (class "Default")
      (node (ref "J1") (pin "5") (pinfunction "5_5") (pintype "passive"))
      (node (ref "U4") (pin "53") (pinfunction "OC6/IC6/CN14/RD5_53") (pintype "passive"))
    )
    (net (code "35") (name "/GPIOD6") (class "Default")
      (node (ref "J1") (pin "3") (pinfunction "3_3") (pintype "passive"))
      (node (ref "U4") (pin "54") (pinfunction "OC7/CN15/RD6_54") (pintype "passive"))
    )
    (net (code "36") (name "/GPIOD7") (class "Default")
      (node (ref "J1") (pin "1") (pinfunction "1_1") (pintype "passive"))
      (node (ref "U4") (pin "55") (pinfunction "OC8/CN16/RD7_55") (pintype "passive"))
    )
    (net (code "37") (name "/GPIOD8") (class "Default")
      (node (ref "J2") (pin "13") (pinfunction "13_13") (pintype "passive"))
      (node (ref "U4") (pin "42") (pinfunction "IC1/INT1/RD8_42") (pintype "passive"))
    )
    (net (code "38") (name "/GPIOD9") (class "Default")
      (node (ref "J2") (pin "11") (pinfunction "11_11") (pintype "passive"))
      (node (ref "U4") (pin "43") (pinfunction "IC2/INT2/RD9_43") (pintype "passive"))
    )
    (net (code "39") (name "/GPIOD10") (class "Default")
      (node (ref "J2") (pin "9") (pinfunction "9_9") (pintype "passive"))
      (node (ref "U4") (pin "44") (pinfunction "IC3/INT3/RD10_44") (pintype "passive"))
    )
    (net (code "40") (name "/GPIOD11") (class "Default")
      (node (ref "J2") (pin "7") (pinfunction "7_7") (pintype "passive"))
      (node (ref "U4") (pin "45") (pinfunction "IC4/INT4/RD11_45") (pintype "passive"))
    )
    (net (code "41") (name "/GROUND") (class "Default")
      (node (ref "D1") (pin "1") (pinfunction "A_1") (pintype "passive"))
      (node (ref "J6") (pin "4") (pinfunction "4_4") (pintype "passive"))
      (node (ref "J7") (pin "4") (pinfunction "4_4") (pintype "passive"))
      (node (ref "Q1") (pin "1") (pinfunction "D_1") (pintype "passive"))
    )
    (net (code "42") (name "/ILUM") (class "Default")
      (node (ref "D7") (pin "3") (pinfunction "C_3") (pintype "passive"))
      (node (ref "J4") (pin "4") (pinfunction "4_4") (pintype "passive"))
      (node (ref "Q4") (pin "3") (pinfunction "G_3") (pintype "passive"))
      (node (ref "R34") (pin "1") (pinfunction "1_1") (pintype "passive"))
    )
    (net (code "43") (name "/IMP") (class "Default")
      (node (ref "C19") (pin "1") (pinfunction "1_1") (pintype "passive"))
      (node (ref "D10") (pin "3") (pinfunction "C_3") (pintype "passive"))
      (node (ref "R36") (pin "2") (pinfunction "2_2") (pintype "passive"))
      (node (ref "R39") (pin "2") (pinfunction "2_2") (pintype "passive"))
      (node (ref "U4") (pin "11") (pinfunction "AN5/IC8/CN7/RB5_11") (pintype "passive"))
    )
    (net (code "44") (name "/IMP_IN") (class "Default")
      (node (ref "J4") (pin "3") (pinfunction "3_3") (pintype "passive"))
      (node (ref "R39") (pin "1") (pinfunction "1_1") (pintype "passive"))
    )
    (net (code "45") (name "/IsFHerror") (class "Default")
      (node (ref "C21") (pin "1") (pinfunction "1_1") (pintype "passive"))
      (node (ref "D12") (pin "3") (pinfunction "C_3") (pintype "passive"))
      (node (ref "R38") (pin "2") (pinfunction "2_2") (pintype "passive"))
      (node (ref "R41") (pin "2") (pinfunction "2_2") (pintype "passive"))
      (node (ref "U4") (pin "32") (pinfunction "U2TX/CN18/RF5_32") (pintype "passive"))
    )
    (net (code "46") (name "/IsFHerror_IN") (class "Default")
      (node (ref "J6") (pin "5") (pinfunction "5_5") (pintype "passive"))
      (node (ref "R41") (pin "1") (pinfunction "1_1") (pintype "passive"))
    )
    (net (code "47") (name "/IsHeating") (class "Default")
      (node (ref "C20") (pin "1") (pinfunction "1_1") (pintype "passive"))
      (node (ref "D11") (pin "3") (pinfunction "C_3") (pintype "passive"))
      (node (ref "R37") (pin "2") (pinfunction "2_2") (pintype "passive"))
      (node (ref "R40") (pin "2") (pinfunction "2_2") (pintype "passive"))
      (node (ref "U4") (pin "31") (pinfunction "U2RX/CN17/RF4_31") (pintype "passive"))
    )
    (net (code "48") (name "/IsHeating_IN") (class "Default")
      (node (ref "J7") (pin "5") (pinfunction "5_5") (pintype "passive"))
      (node (ref "R40") (pin "1") (pinfunction "1_1") (pintype "passive"))
    )
    (net (code "49") (name "/LightD") (class "Default")
      (node (ref "Q2") (pin "3") (pinfunction "G_3") (pintype "passive"))
      (node (ref "R24") (pin "1") (pinfunction "1_1") (pintype "passive"))
      (node (ref "U4") (pin "24") (pinfunction "AN11/RB11_24") (pintype "passive"))
    )
    (net (code "50") (name "/LightD_OUT") (class "Default")
      (node (ref "D3") (pin "1") (pinfunction "A_1") (pintype "passive"))
      (node (ref "J5") (pin "6") (pinfunction "6_6") (pintype "passive"))
      (node (ref "Q2") (pin "1") (pinfunction "D_1") (pintype "passive"))
    )
    (net (code "51") (name "/LightN") (class "Default")
      (node (ref "Q3") (pin "3") (pinfunction "G_3") (pintype "passive"))
      (node (ref "R28") (pin "1") (pinfunction "1_1") (pintype "passive"))
      (node (ref "U4") (pin "27") (pinfunction "AN12/RB12_27") (pintype "passive"))
    )
    (net (code "52") (name "/LightN_OUT") (class "Default")
      (node (ref "D5") (pin "1") (pinfunction "A_1") (pintype "passive"))
      (node (ref "J5") (pin "7") (pinfunction "7_7") (pintype "passive"))
      (node (ref "Q3") (pin "1") (pinfunction "D_1") (pintype "passive"))
    )
    (net (code "53") (name "/LightR") (class "Default")
      (node (ref "Q5") (pin "3") (pinfunction "G_3") (pintype "passive"))
      (node (ref "R35") (pin "1") (pinfunction "1_1") (pintype "passive"))
      (node (ref "U4") (pin "28") (pinfunction "AN13/RB13_28") (pintype "passive"))
    )
    (net (code "54") (name "/LightR_OUT") (class "Default")
      (node (ref "D8") (pin "1") (pinfunction "A_1") (pintype "passive"))
      (node (ref "J5") (pin "8") (pinfunction "8_8") (pintype "passive"))
      (node (ref "Q5") (pin "1") (pinfunction "D_1") (pintype "passive"))
    )
    (net (code "55") (name "/MCLR") (class "Default")
      (node (ref "J3") (pin "1") (pinfunction "1_1") (pintype "passive"))
      (node (ref "R44") (pin "1") (pinfunction "1_1") (pintype "passive"))
      (node (ref "U4") (pin "7") (pinfunction "~{MCLR}_7") (pintype "passive"))
    )
    (net (code "56") (name "/PGC") (class "Default")
      (node (ref "J3") (pin "5") (pinfunction "5_5") (pintype "passive"))
      (node (ref "U4") (pin "17") (pinfunction "PGC/EMUC/AN6/OCFA/RB6_17") (pintype "passive"))
    )
    (net (code "57") (name "/PGD") (class "Default")
      (node (ref "J3") (pin "4") (pinfunction "4_4") (pintype "passive"))
      (node (ref "U4") (pin "18") (pinfunction "PGD/EMUD/AN7/RB7_18") (pintype "passive"))
    )
    (net (code "58") (name "/RESET") (class "Default")
      (node (ref "C23") (pin "2") (pinfunction "2_2") (pintype "passive"))
      (node (ref "D13") (pin "1") (pinfunction "A_1") (pintype "passive"))
      (node (ref "R42") (pin "2") (pinfunction "2_2") (pintype "passive"))
      (node (ref "R44") (pin "2") (pinfunction "2_2") (pintype "passive"))
      (node (ref "U5") (pin "1") (pinfunction "~{RST}_1") (pintype "passive"))
    )
    (net (code "59") (name "/RX") (class "Default")
      (node (ref "J2") (pin "10") (pinfunction "10_10") (pintype "passive"))
      (node (ref "U4") (pin "34") (pinfunction "U1RX/SDI1/RF2_34") (pintype "passive"))
    )
    (net (code "60") (name "/TX") (class "Default")
      (node (ref "J2") (pin "8") (pinfunction "8_8") (pintype "passive"))
      (node (ref "U4") (pin "33") (pinfunction "EMUD3/U1TX/SDO1/RF3_33") (pintype "passive"))
    )
    (net (code "61") (name "/WDI") (class "Default")
      (node (ref "R33") (pin "1") (pinfunction "1_1") (pintype "passive"))
      (node (ref "U5") (pin "4") (pinfunction "WDI_4") (pintype "passive"))
    )
    (net (code "62") (name "GND") (class "Default")
      (node (ref "C1") (pin "2") (pinfunction "2_2") (pintype "passive"))
      (node (ref "C10") (pin "2") (pinfunction "2_2") (pintype "passive"))
      (node (ref "C11") (pin "2") (pinfunction "2_2") (pintype "passive"))
      (node (ref "C12") (pin "2") (pinfunction "2_2") (pintype "passive"))
      (node (ref "C13") (pin "2") (pinfunction "2_2") (pintype "passive"))
      (node (ref "C14") (pin "2") (pinfunction "2_2") (pintype "passive"))
      (node (ref "C15") (pin "2") (pinfunction "2_2") (pintype "passive"))
      (node (ref "C16") (pin "2") (pinfunction "2_2") (pintype "passive"))
      (node (ref "C17") (pin "2") (pinfunction "2_2") (pintype "passive"))
      (node (ref "C18") (pin "2") (pinfunction "2_2") (pintype "passive"))
      (node (ref "C19") (pin "2") (pinfunction "2_2") (pintype "passive"))
      (node (ref "C2") (pin "1") (pinfunction "1_1") (pintype "passive"))
      (node (ref "C20") (pin "2") (pinfunction "2_2") (pintype "passive"))
      (node (ref "C21") (pin "2") (pinfunction "2_2") (pintype "passive"))
      (node (ref "C22") (pin "2") (pinfunction "2_2") (pintype "passive"))
      (node (ref "C23") (pin "1") (pinfunction "1_1") (pintype "passive"))
      (node (ref "C24") (pin "1") (pinfunction "1_1") (pintype "passive"))
      (node (ref "C3") (pin "2") (pinfunction "2_2") (pintype "passive"))
      (node (ref "C4") (pin "2") (pinfunction "2_2") (pintype "passive"))
      (node (ref "C5") (pin "2") (pinfunction "2_2") (pintype "passive"))
      (node (ref "C6") (pin "2") (pinfunction "2_2") (pintype "passive"))
      (node (ref "C7") (pin "1") (pinfunction "1_1") (pintype "passive"))
      (node (ref "C8") (pin "2") (pinfunction "2_2") (pintype "passive"))
      (node (ref "C9") (pin "1") (pinfunction "1_1") (pintype "passive"))
      (node (ref "D10") (pin "1") (pinfunction "A_1") (pintype "passive"))
      (node (ref "D11") (pin "1") (pinfunction "A_1") (pintype "passive"))
      (node (ref "D12") (pin "1") (pinfunction "A_1") (pintype "passive"))
      (node (ref "D2") (pin "1") (pinfunction "A_1") (pintype "passive"))
      (node (ref "D4") (pin "1") (pinfunction "A_1") (pintype "passive"))
      (node (ref "D6") (pin "1") (pinfunction "A_1") (pintype "passive"))
      (node (ref "D7") (pin "1") (pinfunction "A_1") (pintype "passive"))
      (node (ref "D9") (pin "1") (pinfunction "A_1") (pintype "passive"))
      (node (ref "J1") (pin "14") (pinfunction "14_14") (pintype "passive"))
      (node (ref "J2") (pin "12") (pinfunction "12_12") (pintype "passive"))
      (node (ref "J2") (pin "14") (pinfunction "14_14") (pintype "passive"))
      (node (ref "J3") (pin "3") (pinfunction "3_3") (pintype "passive"))
      (node (ref "J4") (pin "1") (pinfunction "1_1") (pintype "passive"))
      (node (ref "J5") (pin "1") (pinfunction "1_1") (pintype "passive"))
      (node (ref "LED4") (pin "2") (pinfunction "K_2") (pintype "passive"))
      (node (ref "Q1") (pin "2") (pinfunction "S_2") (pintype "passive"))
      (node (ref "Q2") (pin "2") (pinfunction "S_2") (pintype "passive"))
      (node (ref "Q3") (pin "2") (pinfunction "S_2") (pintype "passive"))
      (node (ref "Q4") (pin "2") (pinfunction "S_2") (pintype "passive"))
      (node (ref "Q5") (pin "2") (pinfunction "S_2") (pintype "passive"))
      (node (ref "Q6") (pin "2") (pinfunction "S_2") (pintype "passive"))
      (node (ref "Q7") (pin "2") (pinfunction "S_2") (pintype "passive"))
      (node (ref "R1") (pin "1") (pinfunction "1_1") (pintype "passive"))
      (node (ref "R11") (pin "1") (pinfunction "1_1") (pintype "passive"))
      (node (ref "R13") (pin "1") (pinfunction "1_1") (pintype "passive"))
      (node (ref "R14") (pin "2") (pinfunction "2_2") (pintype "passive"))
      (node (ref "R15") (pin "2") (pinfunction "2_2") (pintype "passive"))
      (node (ref "R18") (pin "2") (pinfunction "2_2") (pintype "passive"))
      (node (ref "R2") (pin "2") (pinfunction "2_2") (pintype "passive"))
      (node (ref "R24") (pin "2") (pinfunction "2_2") (pintype "passive"))
      (node (ref "R28") (pin "2") (pinfunction "2_2") (pintype "passive"))
      (node (ref "R34") (pin "2") (pinfunction "2_2") (pintype "passive"))
      (node (ref "R35") (pin "2") (pinfunction "2_2") (pintype "passive"))
      (node (ref "R45") (pin "2") (pinfunction "2_2") (pintype "passive"))
      (node (ref "R46") (pin "2") (pinfunction "2_2") (pintype "passive"))
      (node (ref "R6") (pin "2") (pinfunction "2_2") (pintype "passive"))
      (node (ref "S1") (pin "1") (pintype "passive"))
      (node (ref "U1") (pin "2") (pinfunction "GND_2") (pintype "power_in"))
      (node (ref "U2") (pin "4") (pinfunction "GND_4") (pintype "power_in"))
      (node (ref "U3") (pin "2") (pinfunction "GND_2") (pintype "power_in"))
      (node (ref "U4") (pin "20") (pinfunction "AVSS_20") (pintype "passive"))
      (node (ref "U4") (pin "25") (pinfunction "VSS_25") (pintype "passive"))
      (node (ref "U4") (pin "41") (pinfunction "VSS_41") (pintype "passive"))
      (node (ref "U4") (pin "56") (pinfunction "VSS_56") (pintype "passive"))
      (node (ref "U4") (pin "9") (pinfunction "VSS_9") (pintype "passive"))
      (node (ref "U5") (pin "2") (pinfunction "Vss_2") (pintype "passive"))
    )
    (net (code "63") (name "Net-(C2-Pad2)") (class "Default")
      (node (ref "C2") (pin "2") (pinfunction "2_2") (pintype "passive"))
      (node (ref "R3") (pin "2") (pinfunction "2_2") (pintype "passive"))
      (node (ref "R8") (pin "2") (pinfunction "2_2") (pintype "passive"))
      (node (ref "R9") (pin "2") (pinfunction "2_2") (pintype "passive"))
    )
    (net (code "64") (name "Net-(C9-Pad2)") (class "Default")
      (node (ref "C9") (pin "2") (pinfunction "2_2") (pintype "passive"))
      (node (ref "R16") (pin "2") (pinfunction "2_2") (pintype "passive"))
      (node (ref "R19") (pin "2") (pinfunction "2_2") (pintype "passive"))
      (node (ref "R20") (pin "2") (pinfunction "2_2") (pintype "passive"))
    )
    (net (code "65") (name "Net-(D2-K)") (class "Default")
      (node (ref "D2") (pin "2") (pinfunction "K_2") (pintype "passive"))
      (node (ref "L1") (pin "1") (pinfunction "1_1") (pintype "passive"))
      (node (ref "U2") (pin "2") (pinfunction "SWE_2") (pintype "open_emitter"))
    )
    (net (code "66") (name "Net-(D3-K)") (class "Default")
      (node (ref "D3") (pin "2") (pinfunction "K_2") (pintype "passive"))
      (node (ref "R21") (pin "2") (pinfunction "2_2") (pintype "passive"))
    )
    (net (code "67") (name "Net-(D5-K)") (class "Default")
      (node (ref "D5") (pin "2") (pinfunction "K_2") (pintype "passive"))
      (node (ref "R25") (pin "2") (pinfunction "2_2") (pintype "passive"))
    )
    (net (code "68") (name "Net-(D8-K)") (class "Default")
      (node (ref "D8") (pin "2") (pinfunction "K_2") (pintype "passive"))
      (node (ref "R29") (pin "2") (pinfunction "2_2") (pintype "passive"))
    )
    (net (code "69") (name "Net-(D14-A)") (class "Default")
      (node (ref "C24") (pin "2") (pinfunction "2_2") (pintype "passive"))
      (node (ref "D14") (pin "1") (pinfunction "A_1") (pintype "passive"))
      (node (ref "R43") (pin "1") (pinfunction "1_1") (pintype "passive"))
      (node (ref "S1") (pin "2") (pintype "passive"))
      (node (ref "U5") (pin "3") (pinfunction "~{MR}_3") (pintype "passive"))
    )
    (net (code "70") (name "Net-(LED1-K)") (class "Default")
      (node (ref "LED1") (pin "2") (pinfunction "K_2") (pintype "passive"))
      (node (ref "R5") (pin "1") (pinfunction "1_1") (pintype "passive"))
    )
    (net (code "71") (name "Net-(LED2-K)") (class "Default")
      (node (ref "LED2") (pin "2") (pinfunction "K_2") (pintype "passive"))
      (node (ref "R15") (pin "1") (pinfunction "1_1") (pintype "passive"))
    )
    (net (code "72") (name "Net-(LED3-K)") (class "Default")
      (node (ref "LED3") (pin "2") (pinfunction "K_2") (pintype "passive"))
      (node (ref "R17") (pin "1") (pinfunction "1_1") (pintype "passive"))
    )
    (net (code "73") (name "Net-(LED4-A)") (class "Default")
      (node (ref "LED4") (pin "1") (pinfunction "A_1") (pintype "passive"))
      (node (ref "R12") (pin "2") (pinfunction "2_2") (pintype "passive"))
    )
    (net (code "74") (name "Net-(LED5-K)") (class "Default")
      (node (ref "LED5") (pin "2") (pinfunction "K_2") (pintype "passive"))
      (node (ref "R30") (pin "1") (pinfunction "1_1") (pintype "passive"))
    )
    (net (code "75") (name "Net-(Q1-G)") (class "Default")
      (node (ref "Q1") (pin "3") (pinfunction "G_3") (pintype "passive"))
      (node (ref "R10") (pin "2") (pinfunction "2_2") (pintype "passive"))
    )
    (net (code "76") (name "Net-(Q4-D)") (class "Default")
      (node (ref "Q4") (pin "1") (pinfunction "D_1") (pintype "passive"))
      (node (ref "R21") (pin "1") (pinfunction "1_1") (pintype "passive"))
      (node (ref "R25") (pin "1") (pinfunction "1_1") (pintype "passive"))
      (node (ref "R29") (pin "1") (pinfunction "1_1") (pintype "passive"))
    )
    (net (code "77") (name "Net-(U1-RS)") (class "Default")
      (node (ref "R6") (pin "1") (pinfunction "1_1") (pintype "passive"))
      (node (ref "U1") (pin "8") (pinfunction "RS_8") (pintype "passive"))
    )
    (net (code "78") (name "Net-(U1-VREF)") (class "Default")
      (node (ref "R3") (pin "1") (pinfunction "1_1") (pintype "passive"))
      (node (ref "U1") (pin "5") (pinfunction "VREF_5") (pintype "output"))
    )
    (net (code "79") (name "Net-(U2--VIN)") (class "Default")
      (node (ref "R11") (pin "2") (pinfunction "2_2") (pintype "passive"))
      (node (ref "R7") (pin "2") (pinfunction "2_2") (pintype "passive"))
      (node (ref "U2") (pin "5") (pinfunction "-VIN_5") (pintype "input"))
    )
    (net (code "80") (name "Net-(U2-DRVC)") (class "Default")
      (node (ref "R4") (pin "1") (pinfunction "1_1") (pintype "passive"))
      (node (ref "U2") (pin "1") (pinfunction "SWC_1") (pintype "open_collector"))
      (node (ref "U2") (pin "7") (pinfunction "IPK_7") (pintype "passive"))
      (node (ref "U2") (pin "8") (pinfunction "DRVC_8") (pintype "open_collector"))
    )
    (net (code "81") (name "Net-(U2-TCAP)") (class "Default")
      (node (ref "C7") (pin "2") (pinfunction "2_2") (pintype "passive"))
      (node (ref "U2") (pin "3") (pinfunction "TCAP_3") (pintype "passive"))
    )
    (net (code "82") (name "Net-(U3-RS)") (class "Default")
      (node (ref "R18") (pin "1") (pinfunction "1_1") (pintype "passive"))
      (node (ref "U3") (pin "8") (pinfunction "RS_8") (pintype "passive"))
    )
    (net (code "83") (name "Net-(U3-VREF)") (class "Default")
      (node (ref "R16") (pin "1") (pinfunction "1_1") (pintype "passive"))
      (node (ref "U3") (pin "5") (pinfunction "VREF_5") (pintype "output"))
    )
    (net (code "84") (name "Net-(U4-OSC1{slash}CLKI)") (class "Default")
      (node (ref "C17") (pin "1") (pinfunction "1_1") (pintype "passive"))
      (node (ref "U4") (pin "39") (pinfunction "OSC1/CLKI_39") (pintype "passive"))
      (node (ref "Y1") (pin "2") (pinfunction "OSC2_2") (pintype "passive"))
    )
    (net (code "85") (name "Net-(U4-OSC2{slash}CLKO{slash}RC15)") (class "Default")
      (node (ref "C18") (pin "1") (pinfunction "1_1") (pintype "passive"))
      (node (ref "U4") (pin "40") (pinfunction "OSC2/CLKO/RC15_40") (pintype "passive"))
      (node (ref "Y1") (pin "1") (pinfunction "OSC1_1") (pintype "passive"))
    )
    (net (code "86") (name "Net-(U4-SCL{slash}RG2)") (class "Default")
      (node (ref "R30") (pin "2") (pinfunction "2_2") (pintype "passive"))
      (node (ref "U4") (pin "37") (pinfunction "SCL/RG2_37") (pintype "passive"))
    )
    (net (code "87") (name "Net-(U4-~{SS2}{slash}CN11{slash}RG9)") (class "Default")
      (node (ref "R33") (pin "2") (pinfunction "2_2") (pintype "passive"))
      (node (ref "U4") (pin "8") (pinfunction "~{SS2}/CN11/RG9_8") (pintype "passive"))
    )
    (net (code "88") (name "unconnected-(U1-RXD-Pad4)") (class "Default")
      (node (ref "U1") (pin "4") (pinfunction "RXD_4") (pintype "output+no_connect"))
    )
    (net (code "89") (name "unconnected-(U3-RXD-Pad4)") (class "Default")
      (node (ref "U3") (pin "4") (pinfunction "RXD_4") (pintype "output+no_connect"))
    )
    (net (code "90") (name "unconnected-(U4-COFS{slash}RG15-Pad1)") (class "Default")
      (node (ref "U4") (pin "1") (pinfunction "COFS/RG15_1") (pintype "passive"))
    )
    (net (code "91") (name "unconnected-(U4-CSCK{slash}RG14-Pad62)") (class "Default")
      (node (ref "U4") (pin "62") (pinfunction "CSCK/RG14_62") (pintype "passive"))
    )
    (net (code "92") (name "unconnected-(U4-CSDI{slash}RG12-Pad63)") (class "Default")
      (node (ref "U4") (pin "63") (pinfunction "CSDI/RG12_63") (pintype "passive"))
    )
    (net (code "93") (name "unconnected-(U4-CSDO{slash}RG13-Pad64)") (class "Default")
      (node (ref "U4") (pin "64") (pinfunction "CSDO/RG13_64") (pintype "passive"))
    )
    (net (code "94") (name "unconnected-(U4-EMUC3{slash}SCK1{slash}INT0{slash}RF6-Pad35)") (class "Default")
      (node (ref "U4") (pin "35") (pinfunction "EMUC3/SCK1/INT0/RF6_35") (pintype "passive"))
    )
    (net (code "95") (name "unconnected-(U4-SCK2{slash}CN8{slash}RG6-Pad4)") (class "Default")
      (node (ref "U4") (pin "4") (pinfunction "SCK2/CN8/RG6_4") (pintype "passive"))
    )
    (net (code "96") (name "unconnected-(U4-SDA{slash}RG3-Pad36)") (class "Default")
      (node (ref "U4") (pin "36") (pinfunction "SDA/RG3_36") (pintype "passive"))
    )
    (net (code "97") (name "unconnected-(U4-SDI2{slash}CN9{slash}RG7-Pad5)") (class "Default")
      (node (ref "U4") (pin "5") (pinfunction "SDI2/CN9/RG7_5") (pintype "passive"))
    )
    (net (code "98") (name "unconnected-(U4-SDO2{slash}CN10{slash}RG8-Pad6)") (class "Default")
      (node (ref "U4") (pin "6") (pinfunction "SDO2/CN10/RG8_6") (pintype "passive"))
    )
    (net (code "99") (name "unconnected-(U4-T2CK{slash}RC1-Pad2)") (class "Default")
      (node (ref "U4") (pin "2") (pinfunction "T2CK/RC1_2") (pintype "passive"))
    )
    (net (code "100") (name "unconnected-(U4-T3CK{slash}RC2-Pad3)") (class "Default")
      (node (ref "U4") (pin "3") (pinfunction "T3CK/RC2_3") (pintype "passive"))
    )
  )
)
